# Cart64out_v1.net
KiCad netlist of a schematic drawn in EAGLE
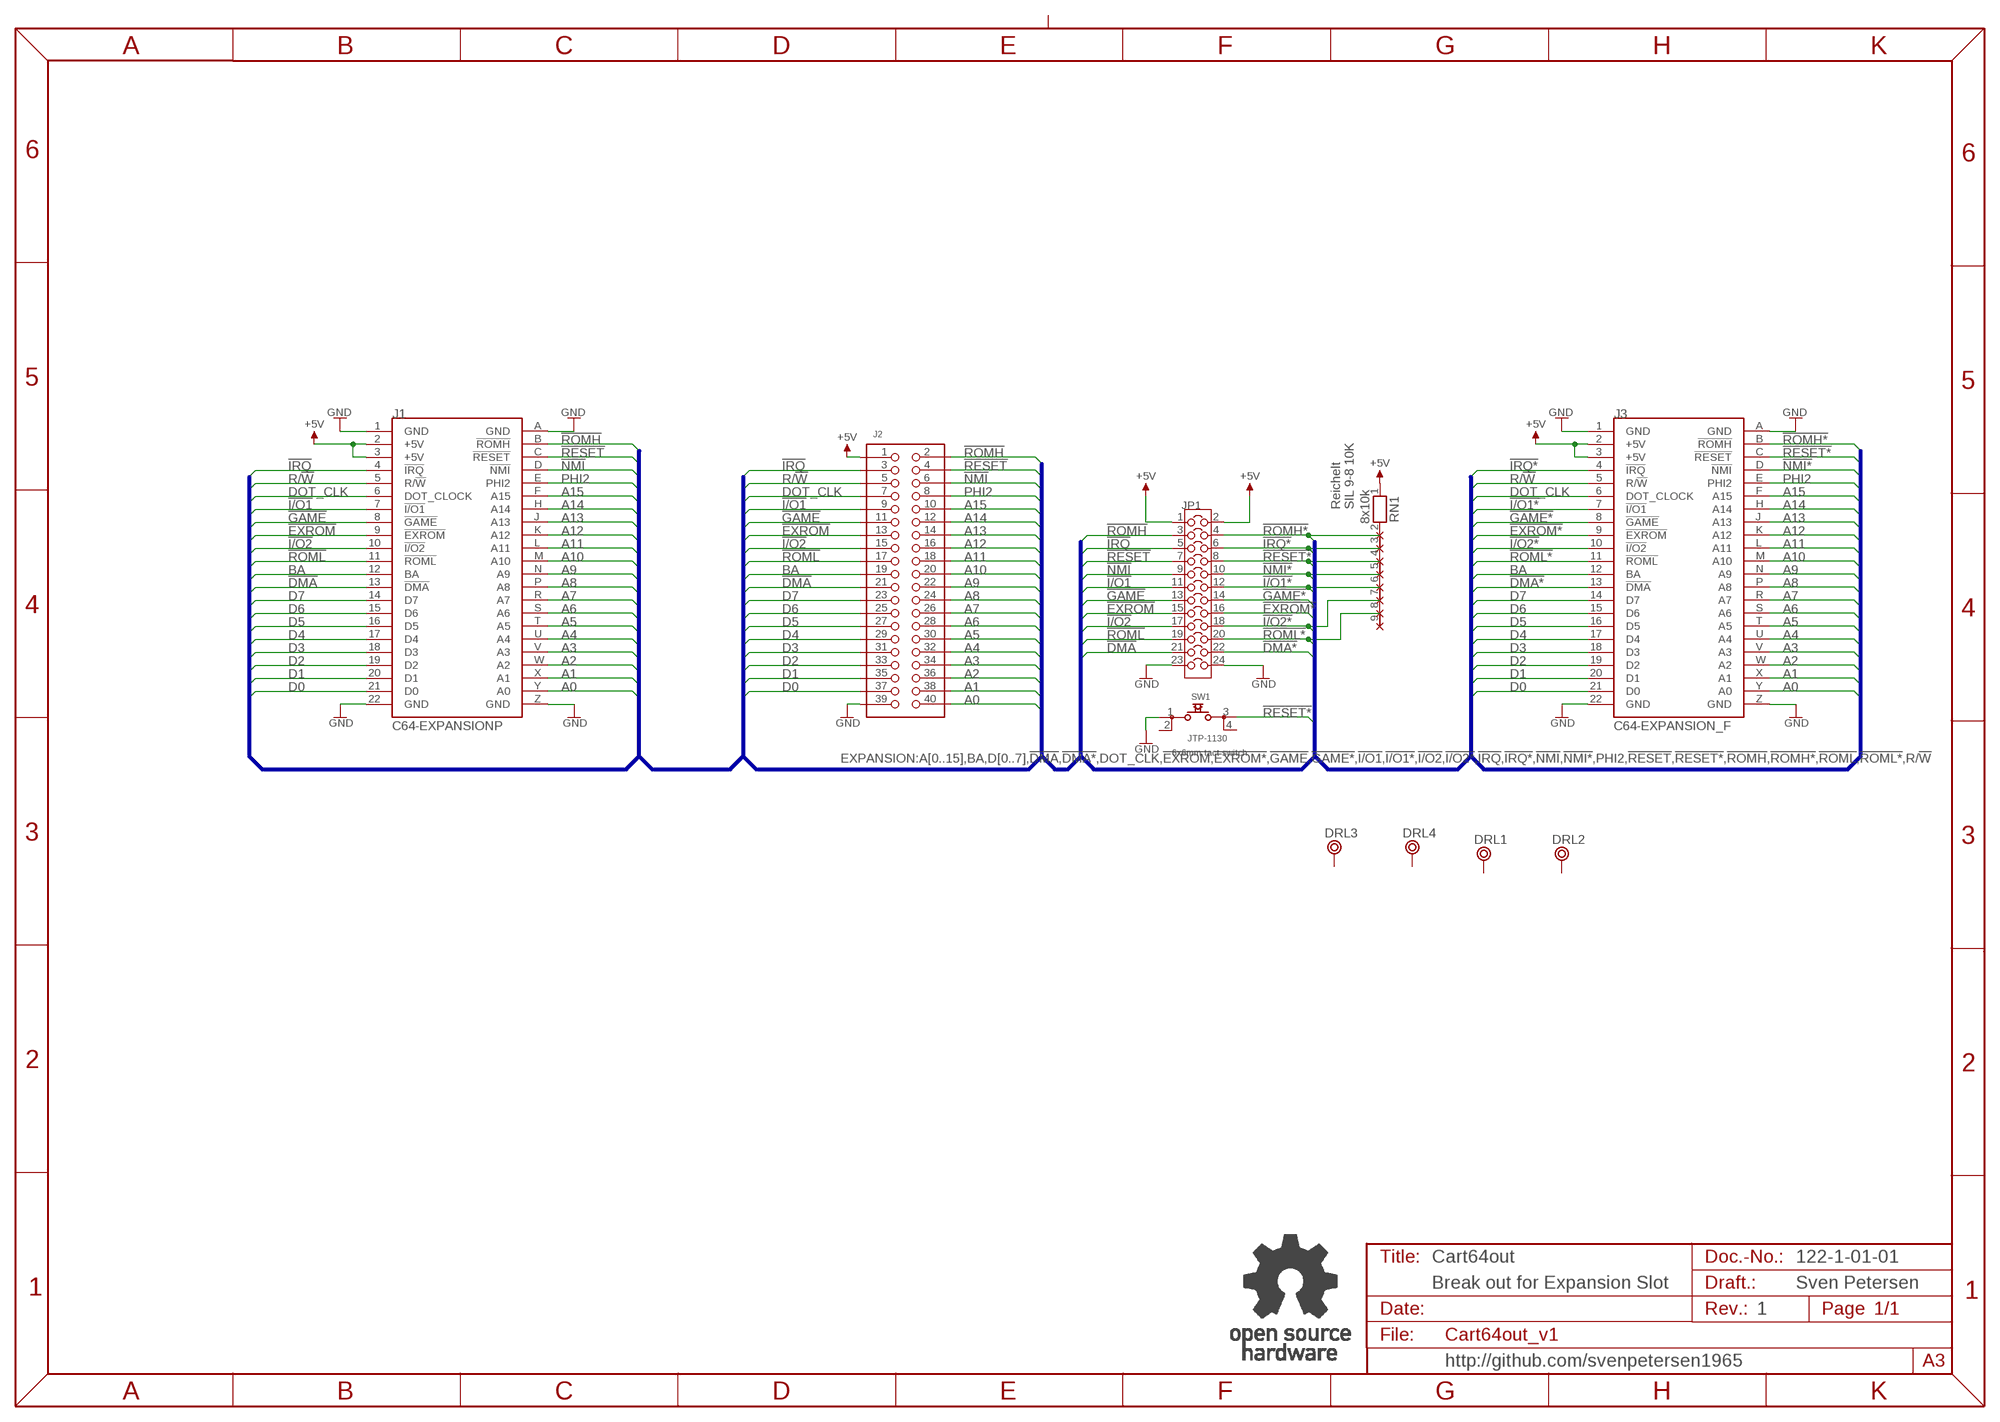
[diagram p0: schematic, sheet 1]

(export (version "E")
  (design (tool "Eeschema 10.0.6"))
  (components
    (comp (ref "DRL1")
      (value "BOHR3,3")
      (footprint "eagle-import:BOHR3,3")
      (libsource (lib "eagle-import") (part "BOHR3,3"))
    )
    (comp (ref "DRL2")
      (value "BOHR3,3")
      (footprint "eagle-import:BOHR3,3")
      (libsource (lib "eagle-import") (part "BOHR3,3"))
    )
    (comp (ref "DRL3")
      (value "BOHR3,3")
      (footprint "eagle-import:BOHR3,3")
      (libsource (lib "eagle-import") (part "BOHR3,3"))
    )
    (comp (ref "DRL4")
      (value "BOHR3,3")
      (footprint "eagle-import:BOHR3,3")
      (libsource (lib "eagle-import") (part "BOHR3,3"))
    )
    (comp (ref "J1")
      (value "C64-EXPANSIONP")
      (footprint "eagle-import:EXPPORT")
      (libsource (lib "eagle-import") (part "C64-EXPANSIONP"))
    )
    (comp (ref "J2")
      (value "PINHD-2X20WV")
      (footprint "eagle-import:2X20WV")
      (libsource (lib "eagle-import") (part "PINHD-2X20WV"))
    )
    (comp (ref "J3")
      (value "C64-EXPANSION_F")
      (footprint "eagle-import:EXPANSION_OUT")
      (libsource (lib "eagle-import") (part "C64-EXPANSION_F"))
    )
    (comp (ref "JP1")
      (value "COMBI_2X12")
      (footprint "eagle-import:COMBI-12X2")
      (libsource (lib "eagle-import") (part "COMBI_2X12"))
    )
    (comp (ref "RN1")
      (value "8x10k")
      (footprint "eagle-import:RN-9")
      (libsource (lib "eagle-import") (part "RN08"))
    )
    (comp (ref "SW1")
      (value "JTP-1130")
      (footprint "eagle-import:JTP-1130")
      (libsource (lib "eagle-import") (part "JTP-1130"))
    )
    (comp (ref "U$22")
      (value "OPEN_SOURCE_HW")
      (footprint "eagle-import:OPENHW")
      (libsource (lib "eagle-import") (part "OPEN_SOURCE_HW"))
    )
  )
  (nets
    (net (code "1") (name "+5V") (class "Default")
      (node (ref "J1") (pin "2") (pinfunction "+5V_2") (pintype "power_in"))
      (node (ref "J1") (pin "3") (pinfunction "+5V_3") (pintype "power_in"))
      (node (ref "J2") (pin "1") (pinfunction "1_1") (pintype "passive"))
      (node (ref "J3") (pin "2") (pinfunction "+5V_2") (pintype "power_in"))
      (node (ref "J3") (pin "3") (pinfunction "+5V_3") (pintype "power_in"))
      (node (ref "JP1") (pin "1") (pinfunction "1_1") (pintype "bidirectional"))
      (node (ref "JP1") (pin "2") (pinfunction "2_2") (pintype "bidirectional"))
      (node (ref "RN1") (pin "1") (pinfunction "1_1") (pintype "passive"))
    )
    (net (code "2") (name "/A0") (class "Default")
      (node (ref "J1") (pin "Y") (pinfunction "A0_Y") (pintype "bidirectional"))
      (node (ref "J2") (pin "40") (pinfunction "40_40") (pintype "passive"))
      (node (ref "J3") (pin "Y") (pinfunction "A0_Y") (pintype "bidirectional"))
    )
    (net (code "3") (name "/A1") (class "Default")
      (node (ref "J1") (pin "X") (pinfunction "A1_X") (pintype "bidirectional"))
      (node (ref "J2") (pin "38") (pinfunction "38_38") (pintype "passive"))
      (node (ref "J3") (pin "X") (pinfunction "A1_X") (pintype "bidirectional"))
    )
    (net (code "4") (name "/A2") (class "Default")
      (node (ref "J1") (pin "W") (pinfunction "A2_W") (pintype "bidirectional"))
      (node (ref "J2") (pin "36") (pinfunction "36_36") (pintype "passive"))
      (node (ref "J3") (pin "W") (pinfunction "A2_W") (pintype "bidirectional"))
    )
    (net (code "5") (name "/A3") (class "Default")
      (node (ref "J1") (pin "V") (pinfunction "A3_V") (pintype "bidirectional"))
      (node (ref "J2") (pin "34") (pinfunction "34_34") (pintype "passive"))
      (node (ref "J3") (pin "V") (pinfunction "A3_V") (pintype "bidirectional"))
    )
    (net (code "6") (name "/A4") (class "Default")
      (node (ref "J1") (pin "U") (pinfunction "A4_U") (pintype "bidirectional"))
      (node (ref "J2") (pin "32") (pinfunction "32_32") (pintype "passive"))
      (node (ref "J3") (pin "U") (pinfunction "A4_U") (pintype "bidirectional"))
    )
    (net (code "7") (name "/A5") (class "Default")
      (node (ref "J1") (pin "T") (pinfunction "A5_T") (pintype "bidirectional"))
      (node (ref "J2") (pin "30") (pinfunction "30_30") (pintype "passive"))
      (node (ref "J3") (pin "T") (pinfunction "A5_T") (pintype "bidirectional"))
    )
    (net (code "8") (name "/A6") (class "Default")
      (node (ref "J1") (pin "S") (pinfunction "A6_S") (pintype "bidirectional"))
      (node (ref "J2") (pin "28") (pinfunction "28_28") (pintype "passive"))
      (node (ref "J3") (pin "S") (pinfunction "A6_S") (pintype "bidirectional"))
    )
    (net (code "9") (name "/A7") (class "Default")
      (node (ref "J1") (pin "R") (pinfunction "A7_R") (pintype "bidirectional"))
      (node (ref "J2") (pin "26") (pinfunction "26_26") (pintype "passive"))
      (node (ref "J3") (pin "R") (pinfunction "A7_R") (pintype "bidirectional"))
    )
    (net (code "10") (name "/A8") (class "Default")
      (node (ref "J1") (pin "P") (pinfunction "A8_P") (pintype "bidirectional"))
      (node (ref "J2") (pin "24") (pinfunction "24_24") (pintype "passive"))
      (node (ref "J3") (pin "P") (pinfunction "A8_P") (pintype "bidirectional"))
    )
    (net (code "11") (name "/A9") (class "Default")
      (node (ref "J1") (pin "N") (pinfunction "A9_N") (pintype "bidirectional"))
      (node (ref "J2") (pin "22") (pinfunction "22_22") (pintype "passive"))
      (node (ref "J3") (pin "N") (pinfunction "A9_N") (pintype "bidirectional"))
    )
    (net (code "12") (name "/A10") (class "Default")
      (node (ref "J1") (pin "M") (pinfunction "A10_M") (pintype "bidirectional"))
      (node (ref "J2") (pin "20") (pinfunction "20_20") (pintype "passive"))
      (node (ref "J3") (pin "M") (pinfunction "A10_M") (pintype "bidirectional"))
    )
    (net (code "13") (name "/A11") (class "Default")
      (node (ref "J1") (pin "L") (pinfunction "A11_L") (pintype "bidirectional"))
      (node (ref "J2") (pin "18") (pinfunction "18_18") (pintype "passive"))
      (node (ref "J3") (pin "L") (pinfunction "A11_L") (pintype "bidirectional"))
    )
    (net (code "14") (name "/A12") (class "Default")
      (node (ref "J1") (pin "K") (pinfunction "A12_K") (pintype "bidirectional"))
      (node (ref "J2") (pin "16") (pinfunction "16_16") (pintype "passive"))
      (node (ref "J3") (pin "K") (pinfunction "A12_K") (pintype "bidirectional"))
    )
    (net (code "15") (name "/A13") (class "Default")
      (node (ref "J1") (pin "J") (pinfunction "A13_J") (pintype "bidirectional"))
      (node (ref "J2") (pin "14") (pinfunction "14_14") (pintype "passive"))
      (node (ref "J3") (pin "J") (pinfunction "A13_J") (pintype "bidirectional"))
    )
    (net (code "16") (name "/A14") (class "Default")
      (node (ref "J1") (pin "H") (pinfunction "A14_H") (pintype "bidirectional"))
      (node (ref "J2") (pin "12") (pinfunction "12_12") (pintype "passive"))
      (node (ref "J3") (pin "H") (pinfunction "A14_H") (pintype "bidirectional"))
    )
    (net (code "17") (name "/A15") (class "Default")
      (node (ref "J1") (pin "F") (pinfunction "A15_F") (pintype "bidirectional"))
      (node (ref "J2") (pin "10") (pinfunction "10_10") (pintype "passive"))
      (node (ref "J3") (pin "F") (pinfunction "A15_F") (pintype "bidirectional"))
    )
    (net (code "18") (name "/BA") (class "Default")
      (node (ref "J1") (pin "12") (pinfunction "BA_12") (pintype "output"))
      (node (ref "J2") (pin "19") (pinfunction "19_19") (pintype "passive"))
      (node (ref "J3") (pin "12") (pinfunction "BA_12") (pintype "output"))
    )
    (net (code "19") (name "/D0") (class "Default")
      (node (ref "J1") (pin "21") (pinfunction "D0_21") (pintype "bidirectional"))
      (node (ref "J2") (pin "37") (pinfunction "37_37") (pintype "passive"))
      (node (ref "J3") (pin "21") (pinfunction "D0_21") (pintype "bidirectional"))
    )
    (net (code "20") (name "/D1") (class "Default")
      (node (ref "J1") (pin "20") (pinfunction "D1_20") (pintype "bidirectional"))
      (node (ref "J2") (pin "35") (pinfunction "35_35") (pintype "passive"))
      (node (ref "J3") (pin "20") (pinfunction "D1_20") (pintype "bidirectional"))
    )
    (net (code "21") (name "/D2") (class "Default")
      (node (ref "J1") (pin "19") (pinfunction "D2_19") (pintype "bidirectional"))
      (node (ref "J2") (pin "33") (pinfunction "33_33") (pintype "passive"))
      (node (ref "J3") (pin "19") (pinfunction "D2_19") (pintype "bidirectional"))
    )
    (net (code "22") (name "/D3") (class "Default")
      (node (ref "J1") (pin "18") (pinfunction "D3_18") (pintype "bidirectional"))
      (node (ref "J2") (pin "31") (pinfunction "31_31") (pintype "passive"))
      (node (ref "J3") (pin "18") (pinfunction "D3_18") (pintype "bidirectional"))
    )
    (net (code "23") (name "/D4") (class "Default")
      (node (ref "J1") (pin "17") (pinfunction "D4_17") (pintype "bidirectional"))
      (node (ref "J2") (pin "29") (pinfunction "29_29") (pintype "passive"))
      (node (ref "J3") (pin "17") (pinfunction "D4_17") (pintype "bidirectional"))
    )
    (net (code "24") (name "/D5") (class "Default")
      (node (ref "J1") (pin "16") (pinfunction "D5_16") (pintype "bidirectional"))
      (node (ref "J2") (pin "27") (pinfunction "27_27") (pintype "passive"))
      (node (ref "J3") (pin "16") (pinfunction "D5_16") (pintype "bidirectional"))
    )
    (net (code "25") (name "/D6") (class "Default")
      (node (ref "J1") (pin "15") (pinfunction "D6_15") (pintype "bidirectional"))
      (node (ref "J2") (pin "25") (pinfunction "25_25") (pintype "passive"))
      (node (ref "J3") (pin "15") (pinfunction "D6_15") (pintype "bidirectional"))
    )
    (net (code "26") (name "/D7") (class "Default")
      (node (ref "J1") (pin "14") (pinfunction "D7_14") (pintype "bidirectional"))
      (node (ref "J2") (pin "23") (pinfunction "23_23") (pintype "passive"))
      (node (ref "J3") (pin "14") (pinfunction "D7_14") (pintype "bidirectional"))
    )
    (net (code "27") (name "/DOT_CLK") (class "Default")
      (node (ref "J1") (pin "6") (pinfunction "DOT_CLOCK_6") (pintype "output"))
      (node (ref "J2") (pin "7") (pinfunction "7_7") (pintype "passive"))
      (node (ref "J3") (pin "6") (pinfunction "DOT_CLOCK_6") (pintype "output"))
    )
    (net (code "28") (name "/PHI2") (class "Default")
      (node (ref "J1") (pin "E") (pinfunction "PHI2_E") (pintype "output"))
      (node (ref "J2") (pin "8") (pinfunction "8_8") (pintype "passive"))
      (node (ref "J3") (pin "E") (pinfunction "PHI2_E") (pintype "output"))
    )
    (net (code "29") (name "/R{slash}~{W}") (class "Default")
      (node (ref "J1") (pin "5") (pinfunction "R/~{W}_5") (pintype "output"))
      (node (ref "J2") (pin "5") (pinfunction "5_5") (pintype "passive"))
      (node (ref "J3") (pin "5") (pinfunction "R/~{W}_5") (pintype "output"))
    )
    (net (code "31") (name "/~{DMA*}") (class "Default")
      (node (ref "J3") (pin "13") (pinfunction "~{DMA}_13") (pintype "input"))
      (node (ref "JP1") (pin "22") (pinfunction "22_22") (pintype "bidirectional"))
    )
    (net (code "32") (name "/~{DMA}") (class "Default")
      (node (ref "J1") (pin "13") (pinfunction "~{DMA}_13") (pintype "input"))
      (node (ref "J2") (pin "21") (pinfunction "21_21") (pintype "passive"))
      (node (ref "JP1") (pin "21") (pinfunction "21_21") (pintype "bidirectional"))
    )
    (net (code "33") (name "/~{EXROM*}") (class "Default")
      (node (ref "J3") (pin "9") (pinfunction "~{EXROM}_9") (pintype "input"))
      (node (ref "JP1") (pin "16") (pinfunction "16_16") (pintype "bidirectional"))
    )
    (net (code "34") (name "/~{EXROM}") (class "Default")
      (node (ref "J1") (pin "9") (pinfunction "~{EXROM}_9") (pintype "input"))
      (node (ref "J2") (pin "13") (pinfunction "13_13") (pintype "passive"))
      (node (ref "JP1") (pin "15") (pinfunction "15_15") (pintype "bidirectional"))
    )
    (net (code "35") (name "/~{GAME*}") (class "Default")
      (node (ref "J3") (pin "8") (pinfunction "~{GAME}_8") (pintype "input"))
      (node (ref "JP1") (pin "14") (pinfunction "14_14") (pintype "bidirectional"))
    )
    (net (code "36") (name "/~{GAME}") (class "Default")
      (node (ref "J1") (pin "8") (pinfunction "~{GAME}_8") (pintype "input"))
      (node (ref "J2") (pin "11") (pinfunction "11_11") (pintype "passive"))
      (node (ref "JP1") (pin "13") (pinfunction "13_13") (pintype "bidirectional"))
    )
    (net (code "37") (name "/~{IRQ*}") (class "Default")
      (node (ref "J3") (pin "4") (pinfunction "~{IRQ}_4") (pintype "input"))
      (node (ref "JP1") (pin "6") (pinfunction "6_6") (pintype "bidirectional"))
      (node (ref "RN1") (pin "3") (pinfunction "3_3") (pintype "passive"))
    )
    (net (code "38") (name "/~{IRQ}") (class "Default")
      (node (ref "J1") (pin "4") (pinfunction "~{IRQ}_4") (pintype "input"))
      (node (ref "J2") (pin "3") (pinfunction "3_3") (pintype "passive"))
      (node (ref "JP1") (pin "5") (pinfunction "5_5") (pintype "bidirectional"))
    )
    (net (code "39") (name "/~{I{slash}O1*}") (class "Default")
      (node (ref "J3") (pin "7") (pinfunction "~{I/O1}_7") (pintype "output"))
      (node (ref "JP1") (pin "12") (pinfunction "12_12") (pintype "bidirectional"))
      (node (ref "RN1") (pin "6") (pinfunction "6_6") (pintype "passive"))
    )
    (net (code "40") (name "/~{I{slash}O1}") (class "Default")
      (node (ref "J1") (pin "7") (pinfunction "~{I/O1}_7") (pintype "output"))
      (node (ref "J2") (pin "9") (pinfunction "9_9") (pintype "passive"))
      (node (ref "JP1") (pin "11") (pinfunction "11_11") (pintype "bidirectional"))
    )
    (net (code "41") (name "/~{I{slash}O2*}") (class "Default")
      (node (ref "J3") (pin "10") (pinfunction "~{I/O2}_10") (pintype "output"))
      (node (ref "JP1") (pin "18") (pinfunction "18_18") (pintype "bidirectional"))
      (node (ref "RN1") (pin "7") (pinfunction "7_7") (pintype "passive"))
    )
    (net (code "42") (name "/~{I{slash}O2}") (class "Default")
      (node (ref "J1") (pin "10") (pinfunction "~{I/O2}_10") (pintype "output"))
      (node (ref "J2") (pin "15") (pinfunction "15_15") (pintype "passive"))
      (node (ref "JP1") (pin "17") (pinfunction "17_17") (pintype "bidirectional"))
    )
    (net (code "43") (name "/~{NMI*}") (class "Default")
      (node (ref "J3") (pin "D") (pinfunction "~{NMI}_D") (pintype "input"))
      (node (ref "JP1") (pin "10") (pinfunction "10_10") (pintype "bidirectional"))
      (node (ref "RN1") (pin "5") (pinfunction "5_5") (pintype "passive"))
    )
    (net (code "44") (name "/~{NMI}") (class "Default")
      (node (ref "J1") (pin "D") (pinfunction "~{NMI}_D") (pintype "input"))
      (node (ref "J2") (pin "6") (pinfunction "6_6") (pintype "passive"))
      (node (ref "JP1") (pin "9") (pinfunction "9_9") (pintype "bidirectional"))
    )
    (net (code "45") (name "/~{RESET*}") (class "Default")
      (node (ref "J3") (pin "C") (pinfunction "~{RESET}_C") (pintype "open_collector"))
      (node (ref "JP1") (pin "8") (pinfunction "8_8") (pintype "bidirectional"))
      (node (ref "RN1") (pin "4") (pinfunction "4_4") (pintype "passive"))
      (node (ref "SW1") (pin "3") (pinfunction "3_3") (pintype "passive"))
    )
    (net (code "46") (name "/~{RESET}") (class "Default")
      (node (ref "J1") (pin "C") (pinfunction "~{RESET}_C") (pintype "open_collector"))
      (node (ref "J2") (pin "4") (pinfunction "4_4") (pintype "passive"))
      (node (ref "JP1") (pin "7") (pinfunction "7_7") (pintype "bidirectional"))
    )
    (net (code "47") (name "/~{ROMH*}") (class "Default")
      (node (ref "J3") (pin "B") (pinfunction "~{ROMH}_B") (pintype "output"))
      (node (ref "JP1") (pin "4") (pinfunction "4_4") (pintype "bidirectional"))
      (node (ref "RN1") (pin "2") (pinfunction "2_2") (pintype "passive"))
    )
    (net (code "48") (name "/~{ROMH}") (class "Default")
      (node (ref "J1") (pin "B") (pinfunction "~{ROMH}_B") (pintype "output"))
      (node (ref "J2") (pin "2") (pinfunction "2_2") (pintype "passive"))
      (node (ref "JP1") (pin "3") (pinfunction "3_3") (pintype "bidirectional"))
    )
    (net (code "49") (name "/~{ROML*}") (class "Default")
      (node (ref "J3") (pin "11") (pinfunction "~{ROML}_11") (pintype "output"))
      (node (ref "JP1") (pin "20") (pinfunction "20_20") (pintype "bidirectional"))
      (node (ref "RN1") (pin "8") (pinfunction "8_8") (pintype "passive"))
    )
    (net (code "50") (name "/~{ROML}") (class "Default")
      (node (ref "J1") (pin "11") (pinfunction "~{ROML}_11") (pintype "output"))
      (node (ref "J2") (pin "17") (pinfunction "17_17") (pintype "passive"))
      (node (ref "JP1") (pin "19") (pinfunction "19_19") (pintype "bidirectional"))
    )
    (net (code "51") (name "GND") (class "Default")
      (node (ref "J1") (pin "1") (pinfunction "GND_1") (pintype "power_in"))
      (node (ref "J1") (pin "22") (pinfunction "GND_22") (pintype "power_in"))
      (node (ref "J1") (pin "A") (pinfunction "GND_A") (pintype "power_in"))
      (node (ref "J1") (pin "Z") (pinfunction "GND_Z") (pintype "power_in"))
      (node (ref "J2") (pin "39") (pinfunction "39_39") (pintype "passive"))
      (node (ref "J3") (pin "1") (pinfunction "GND_1") (pintype "power_in"))
      (node (ref "J3") (pin "22") (pinfunction "GND_22") (pintype "power_in"))
      (node (ref "J3") (pin "A") (pinfunction "GND_A") (pintype "power_in"))
      (node (ref "J3") (pin "Z") (pinfunction "GND_Z") (pintype "power_in"))
      (node (ref "JP1") (pin "23") (pinfunction "23_23") (pintype "bidirectional"))
      (node (ref "JP1") (pin "24") (pinfunction "24_24") (pintype "bidirectional"))
      (node (ref "SW1") (pin "1") (pinfunction "1_1") (pintype "passive"))
    )
    (net (code "52") (name "unconnected-(DRL1-PadP$1)") (class "Default")
      (node (ref "DRL1") (pin "P$1") (pinfunction "P$1_P$1") (pintype "passive"))
    )
    (net (code "53") (name "unconnected-(DRL2-PadP$1)") (class "Default")
      (node (ref "DRL2") (pin "P$1") (pinfunction "P$1_P$1") (pintype "passive"))
    )
    (net (code "54") (name "unconnected-(DRL3-PadP$1)") (class "Default")
      (node (ref "DRL3") (pin "P$1") (pinfunction "P$1_P$1") (pintype "passive"))
    )
    (net (code "55") (name "unconnected-(DRL4-PadP$1)") (class "Default")
      (node (ref "DRL4") (pin "P$1") (pinfunction "P$1_P$1") (pintype "passive"))
    )
    (net (code "56") (name "unconnected-(RN1-Pad9)") (class "Default")
      (node (ref "RN1") (pin "9") (pinfunction "9_9") (pintype "passive"))
    )
    (net (code "57") (name "unconnected-(SW1-Pad2)") (class "Default")
      (node (ref "SW1") (pin "2") (pinfunction "2_2") (pintype "passive"))
    )
    (net (code "58") (name "unconnected-(SW1-Pad4)") (class "Default")
      (node (ref "SW1") (pin "4") (pinfunction "4_4") (pintype "passive"))
    )
  )
)
